# ExternalConnectors.net
KiCad netlist of a schematic drawn in Altium Designer
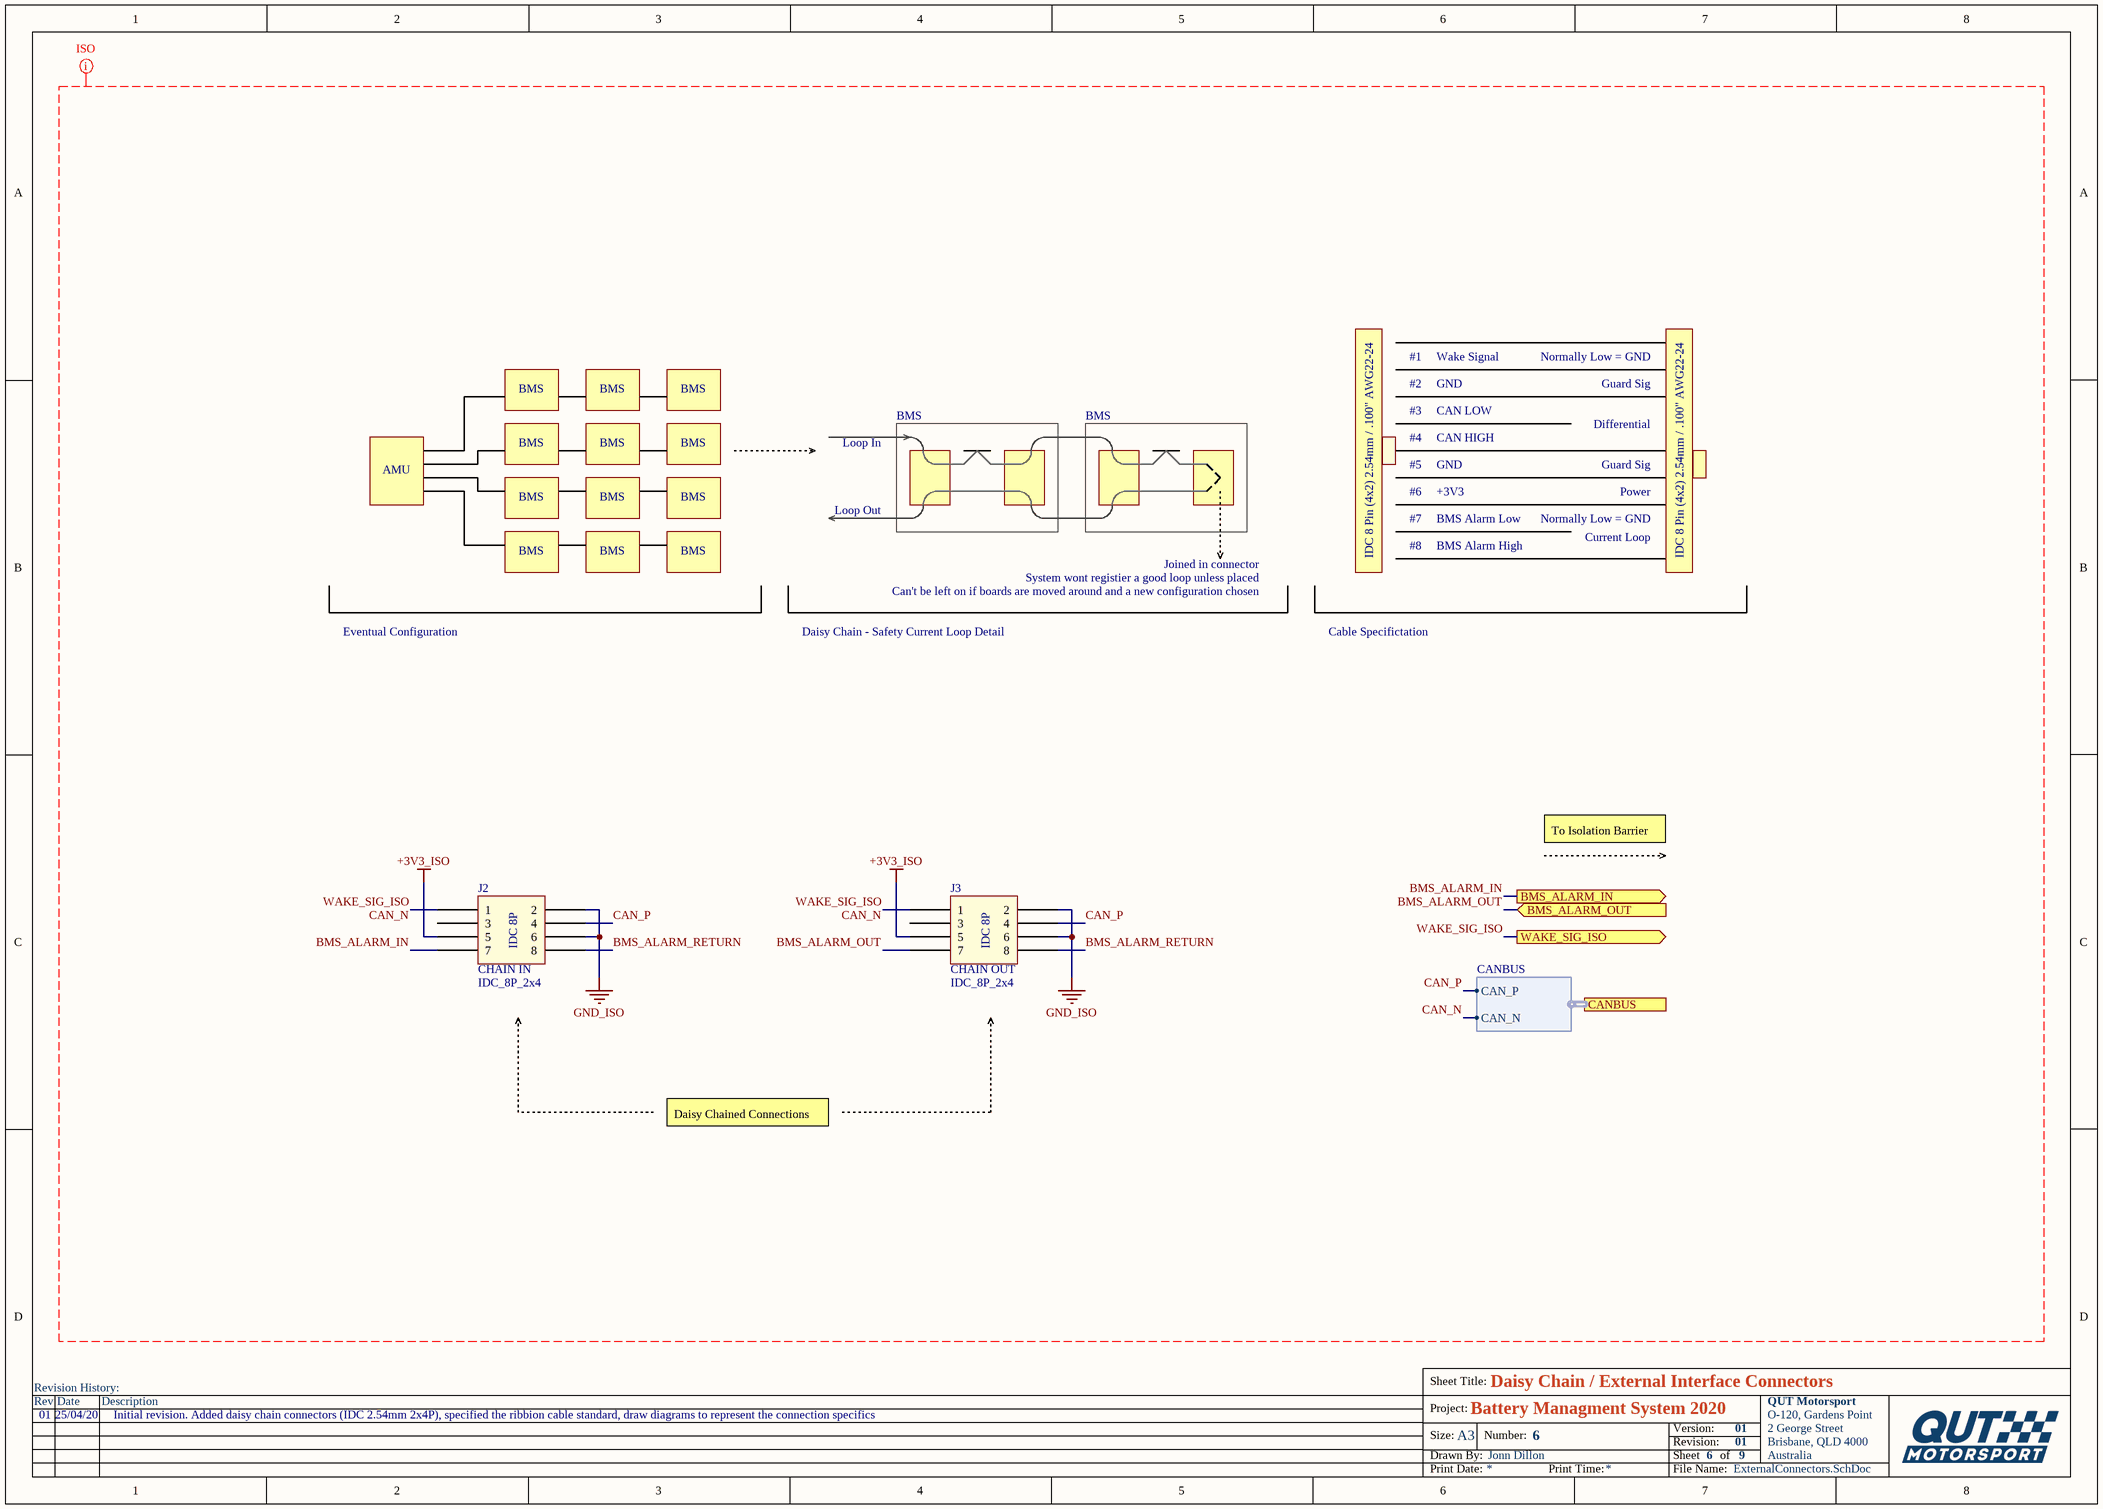
[diagram p0: ExternalConnectors.SchDoc]

(export (version "E")
  (design (tool "Eeschema 10.0.6"))
  (components
    (comp (ref "J2")
      (value "CHAIN IN")
      (footprint "IDC_8P")
      (libsource (lib "IDCConnectors") (part "IDC_8P_2x5"))
    )
    (comp (ref "J3")
      (value "CHAIN OUT")
      (footprint "IDC_8P")
      (libsource (lib "IDCConnectors") (part "IDC_8P_2x5"))
    )
  )
  (nets
    (net (code "2") (name "+3V3_ISO") (class "Default")
      (node (ref "J2") (pin "5") (pinfunction "5_5") (pintype "passive"))
      (node (ref "J3") (pin "5") (pinfunction "5_5") (pintype "passive"))
    )
    (net (code "3") (name "/BMS_ALARM_IN") (class "Default")
      (node (ref "J2") (pin "7") (pinfunction "7_7") (pintype "passive"))
    )
    (net (code "4") (name "/BMS_ALARM_OUT") (class "Default")
      (node (ref "J3") (pin "7") (pinfunction "7_7") (pintype "passive"))
    )
    (net (code "5") (name "/BMS_ALARM_RETURN") (class "Default")
      (node (ref "J2") (pin "8") (pinfunction "8_8") (pintype "passive"))
      (node (ref "J3") (pin "8") (pinfunction "8_8") (pintype "passive"))
    )
    (net (code "7") (name "/CAN_P") (class "Default")
      (node (ref "J2") (pin "4") (pinfunction "4_4") (pintype "passive"))
      (node (ref "J3") (pin "4") (pinfunction "4_4") (pintype "passive"))
    )
    (net (code "8") (name "/WAKE_SIG_ISO") (class "Default")
      (node (ref "J2") (pin "1") (pinfunction "1_1") (pintype "passive"))
      (node (ref "J3") (pin "1") (pinfunction "1_1") (pintype "passive"))
    )
    (net (code "10") (name "GND_ISO") (class "Default")
      (node (ref "J2") (pin "2") (pinfunction "2_2") (pintype "passive"))
      (node (ref "J2") (pin "6") (pinfunction "6_6") (pintype "passive"))
      (node (ref "J3") (pin "2") (pinfunction "2_2") (pintype "passive"))
      (node (ref "J3") (pin "6") (pinfunction "6_6") (pintype "passive"))
    )
    (net (code "11") (name "unconnected-(J2-Pad3)") (class "Default")
      (node (ref "J2") (pin "3") (pinfunction "3_3") (pintype "passive"))
    )
    (net (code "12") (name "unconnected-(J3-Pad3)") (class "Default")
      (node (ref "J3") (pin "3") (pinfunction "3_3") (pintype "passive"))
    )
  )
)
